# CTR-Lower-Main-Board-Rev-B-Sensors-4.net
KiCad netlist of a schematic drawn in Altium Designer
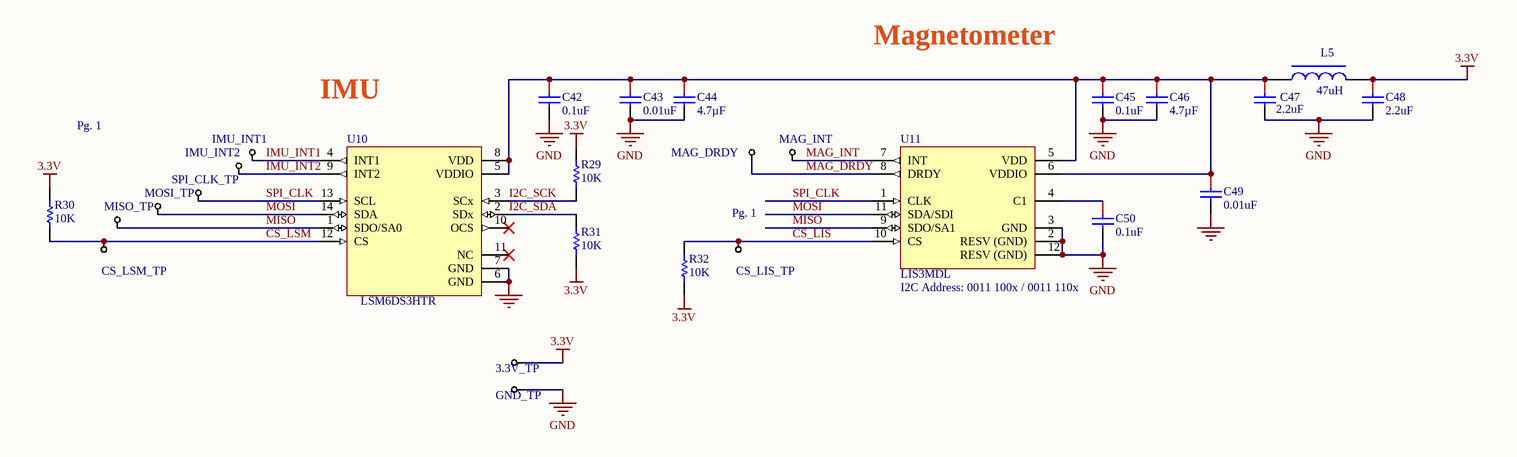
[diagram p0: CTR-Lower-Main-Board-Rev-B-Sensors-4.SchDoc]

(export (version "E")
  (design (tool "Eeschema 10.0.6"))
  (components
    (comp (ref "3.3V_TP")
      (value "3V")
      (footprint "TestPoint-TH 35 mil")
      (description "Test Point")
      (libsource (lib "OLogic-Misc") (part "TestPoint, small"))
    )
    (comp (ref "C42")
      (value "0.1uF")
      (footprint "CAPC0402(1005)_N")
      (description "0.1uF 0402 50V")
      (fields
        (field (name "MANUFACTURER") "TDK Corporation")
        (field (name "MANUFACTURER PART NUMBER") "CGA2B3X7R1H104K050BB")
        (field (name "CREATOR") "osman")
      )
      (libsource (lib "OLogic-Passive") (part "CAP CER 0.1UF 50V 10% X7R 0402"))
    )
    (comp (ref "C43")
      (value "0.01uF")
      (footprint "CAPC0402(1005)_N")
      (description "0.01uF 0402")
      (fields
        (field (name "MANUFACTURER") "Murata Electronics North America")
        (field (name "MANUFACTURER PART NUMBER") "GRM155R71E103KA01D")
      )
      (libsource (lib "OLogic-Passive") (part "CAP CER 0.01UF 25V 10% X5R 0402"))
    )
    (comp (ref "C44")
      (value "4.7UF 0603")
      (footprint "CAPC0603(1608)_L")
      (fields
        (field (name "MANUFACTURER") "Taiyo Yuden")
        (field (name "MANUFACTURER PART NUMBER") "EMK107ABJ475KA-T")
        (field (name "TOLERANCE") "±10%")
        (field (name "CAPACITANCE") "4.7µF")
        (field (name "CREATOR") "osman")
      )
      (libsource (lib "OLogic-Passive") (part "CAP CER 4.7UF 16V 10% X5R 0603"))
    )
    (comp (ref "C45")
      (value "0.1uF")
      (footprint "CAPC0402(1005)_N")
      (description "0.1uF 0402 50V")
      (fields
        (field (name "MANUFACTURER") "TDK Corporation")
        (field (name "MANUFACTURER PART NUMBER") "CGA2B3X7R1H104K050BB")
        (field (name "CREATOR") "osman")
      )
      (libsource (lib "OLogic-Passive") (part "CAP CER 0.1UF 50V 10% X7R 0402"))
    )
    (comp (ref "C46")
      (value "4.7UF 0603")
      (footprint "CAPC0603(1608)_L")
      (fields
        (field (name "MANUFACTURER") "Taiyo Yuden")
        (field (name "MANUFACTURER PART NUMBER") "EMK107ABJ475KA-T")
        (field (name "TOLERANCE") "±10%")
        (field (name "CAPACITANCE") "4.7µF")
        (field (name "CREATOR") "osman")
      )
      (libsource (lib "OLogic-Passive") (part "CAP CER 4.7UF 16V 10% X5R 0603"))
    )
    (comp (ref "C47")
      (value "2.2uF")
      (footprint "CAPC0402(1005)_N")
      (description "2.2uF 0402")
      (fields
        (field (name "MANUFACTURER") "TDK Corporation")
        (field (name "MANUFACTURER PART NUMBER") "C1005X5R1V225K050BC")
        (field (name "CREATOR") "osman")
      )
      (libsource (lib "OLogic-Passive") (part "CAP CER 2.2UF 35V 10% X5R 0402"))
    )
    (comp (ref "C48")
      (value "2.2uF")
      (footprint "CAPC0402(1005)_N")
      (description "2.2uF 0402")
      (fields
        (field (name "MANUFACTURER") "TDK Corporation")
        (field (name "MANUFACTURER PART NUMBER") "C1005X5R1V225K050BC")
        (field (name "CREATOR") "osman")
      )
      (libsource (lib "OLogic-Passive") (part "CAP CER 2.2UF 35V 10% X5R 0402"))
    )
    (comp (ref "C49")
      (value "0.01uF")
      (footprint "CAPC0402(1005)_N")
      (description "0.01uF 0402")
      (fields
        (field (name "MANUFACTURER") "Murata Electronics North America")
        (field (name "MANUFACTURER PART NUMBER") "GRM155R71E103KA01D")
      )
      (libsource (lib "OLogic-Passive") (part "CAP CER 0.01UF 25V 10% X5R 0402"))
    )
    (comp (ref "C50")
      (value "0.1uF")
      (footprint "CAPC0402(1005)_N")
      (description "0.1uF 0402 50V")
      (fields
        (field (name "MANUFACTURER") "TDK Corporation")
        (field (name "MANUFACTURER PART NUMBER") "CGA2B3X7R1H104K050BB")
        (field (name "CREATOR") "osman")
      )
      (libsource (lib "OLogic-Passive") (part "CAP CER 0.1UF 50V 10% X7R 0402"))
    )
    (comp (ref "CS_LIS_TP")
      (value "Test Point")
      (footprint "TestPoint-TH 42 mil")
      (libsource (lib "OLogic-Misc") (part "TestPoint, small"))
    )
    (comp (ref "CS_LSM_TP")
      (value "Test Point")
      (footprint "TestPoint-TH 42 mil")
      (libsource (lib "OLogic-Misc") (part "TestPoint, small"))
    )
    (comp (ref "GND_TP")
      (value "GND")
      (footprint "TestPoint-TH 35 mil")
      (description "Test Point")
      (libsource (lib "OLogic-Misc") (part "TestPoint, small"))
    )
    (comp (ref "IMU_INT1")
      (value "Test Point")
      (footprint "TestPoint-TH 42 mil")
      (libsource (lib "OLogic-Misc") (part "TestPoint, small"))
    )
    (comp (ref "IMU_INT2")
      (value "Test Point")
      (footprint "TestPoint-TH 42 mil")
      (libsource (lib "OLogic-Misc") (part "TestPoint, small"))
    )
    (comp (ref "L5")
      (value "47uH")
      (footprint "IND-2012 Chip")
      (description "47uH 0805")
      (fields
        (field (name "MANUFACTURER") "TDK Corporation")
        (field (name "MANUFACTURER PART NUMBER") "MLZ2012M470WT000")
      )
      (libsource (lib "OLogic-Passive") (part "INDUCTOR MULTILAYER 47UH 100mA 0805"))
    )
    (comp (ref "MAG_DRDY")
      (value "Test Point")
      (footprint "TestPoint-TH 42 mil")
      (libsource (lib "OLogic-Misc") (part "TestPoint, small"))
    )
    (comp (ref "MAG_INT")
      (value "Test Point")
      (footprint "TestPoint-TH 42 mil")
      (libsource (lib "OLogic-Misc") (part "TestPoint, small"))
    )
    (comp (ref "MISO_TP")
      (value "Test Point")
      (footprint "TestPoint-TH 42 mil")
      (libsource (lib "OLogic-Misc") (part "TestPoint, small"))
    )
    (comp (ref "MOSI_TP")
      (value "Test Point")
      (footprint "TestPoint-TH 42 mil")
      (libsource (lib "OLogic-Misc") (part "TestPoint, small"))
    )
    (comp (ref "R29")
      (value "10K")
      (footprint "RESC0402(1005)_N")
      (description "10K 0402")
      (fields
        (field (name "MANUFACTURER") "Panasonic Electronic Components")
        (field (name "MANUFACTURER PART NUMBER") "ERJ-2GEJ103X")
        (field (name "CREATOR") "ted")
      )
      (libsource (lib "OLogic-Passive") (part "RES 10K OHM 5% 1/10W 0402"))
    )
    (comp (ref "R30")
      (value "10K")
      (footprint "RESC0402(1005)_N")
      (description "10K 0402")
      (fields
        (field (name "MANUFACTURER") "Panasonic Electronic Components")
        (field (name "MANUFACTURER PART NUMBER") "ERJ-2GEJ103X")
        (field (name "CREATOR") "ted")
      )
      (libsource (lib "OLogic-Passive") (part "RES 10K OHM 5% 1/10W 0402"))
    )
    (comp (ref "R31")
      (value "10K")
      (footprint "RESC0402(1005)_N")
      (description "10K 0402")
      (fields
        (field (name "MANUFACTURER") "Panasonic Electronic Components")
        (field (name "MANUFACTURER PART NUMBER") "ERJ-2GEJ103X")
        (field (name "CREATOR") "ted")
      )
      (libsource (lib "OLogic-Passive") (part "RES 10K OHM 5% 1/10W 0402"))
    )
    (comp (ref "R32")
      (value "10K")
      (footprint "RESC0402(1005)_N")
      (description "10K 0402")
      (fields
        (field (name "MANUFACTURER") "Panasonic Electronic Components")
        (field (name "MANUFACTURER PART NUMBER") "ERJ-2GEJ103X")
        (field (name "CREATOR") "ted")
      )
      (libsource (lib "OLogic-Passive") (part "RES 10K OHM 5% 1/10W 0402"))
    )
    (comp (ref "SPI_CLK_TP")
      (value "Test Point")
      (footprint "TestPoint-TH 42 mil")
      (libsource (lib "OLogic-Misc") (part "TestPoint, small"))
    )
    (comp (ref "U10")
      (value "LSM6DS3")
      (footprint "LSM6DS3")
      (description "IMU ACCEL/GYRO/TEMP I2C/SPI LGA")
      (fields
        (field (name "MANUFACTURER") "STMicroelectronics")
        (field (name "MANUFACTURER PART NUMBER") "LSM6DS3HTR")
      )
      (libsource (lib "OLogic-Sensors") (part "LSM6DS3"))
    )
    (comp (ref "U11")
      (value "LIS3MDL")
      (footprint "LIS3MDL")
      (description "IC MAGNETOMETER 3-AXIS 12LGA")
      (fields
        (field (name "MANUFACTURER") "STMicroelectronics")
        (field (name "MANUFACTURER PART NUMBER") "LIS3MDL")
        (field (name "I2C ADDRESS") "0011 100x / 0011 110x")
        (field (name "CREATOR") "osman")
      )
      (libsource (lib "OLogic-Sensors") (part "LIS3MDL"))
    )
  )
  (nets
    (net (code "1") (name "/CS_LIS") (class "Default")
      (node (ref "CS_LIS_TP") (pin "1") (pinfunction "1_1") (pintype "passive"))
      (node (ref "R32") (pin "2") (pinfunction "2_2") (pintype "passive"))
      (node (ref "U11") (pin "10") (pinfunction "CS_10") (pintype "input"))
    )
    (net (code "2") (name "/CS_LSM") (class "Default")
      (node (ref "CS_LSM_TP") (pin "1") (pinfunction "1_1") (pintype "passive"))
      (node (ref "R30") (pin "1") (pinfunction "1_1") (pintype "passive"))
      (node (ref "U10") (pin "12") (pinfunction "CS_12") (pintype "input"))
    )
    (net (code "3") (name "/I2C_SCK") (class "Default")
      (node (ref "R29") (pin "1") (pinfunction "1_1") (pintype "passive"))
      (node (ref "U10") (pin "3") (pinfunction "SCx_3") (pintype "input"))
    )
    (net (code "4") (name "/I2C_SDA") (class "Default")
      (node (ref "R31") (pin "2") (pinfunction "2_2") (pintype "passive"))
      (node (ref "U10") (pin "2") (pinfunction "SDx_2") (pintype "bidirectional"))
    )
    (net (code "5") (name "/IMU_INT1") (class "Default")
      (node (ref "IMU_INT1") (pin "1") (pinfunction "1_1") (pintype "passive"))
      (node (ref "U10") (pin "4") (pinfunction "INT1_4") (pintype "output"))
    )
    (net (code "6") (name "/IMU_INT2") (class "Default")
      (node (ref "IMU_INT2") (pin "1") (pinfunction "1_1") (pintype "passive"))
      (node (ref "U10") (pin "9") (pinfunction "INT2_9") (pintype "output"))
    )
    (net (code "7") (name "/MAG_DRDY") (class "Default")
      (node (ref "MAG_DRDY") (pin "1") (pinfunction "1_1") (pintype "passive"))
      (node (ref "U11") (pin "8") (pinfunction "DRDY_8") (pintype "output"))
    )
    (net (code "8") (name "/MAG_INT") (class "Default")
      (node (ref "MAG_INT") (pin "1") (pinfunction "1_1") (pintype "passive"))
      (node (ref "U11") (pin "7") (pinfunction "INT_7") (pintype "output"))
    )
    (net (code "9") (name "/MISO") (class "Default")
      (node (ref "MISO_TP") (pin "1") (pinfunction "1_1") (pintype "passive"))
      (node (ref "U10") (pin "1") (pinfunction "SDO/SA0_1") (pintype "bidirectional"))
      (node (ref "U11") (pin "9") (pinfunction "SDO/SA1_9") (pintype "bidirectional"))
    )
    (net (code "10") (name "/MOSI") (class "Default")
      (node (ref "MOSI_TP") (pin "1") (pinfunction "1_1") (pintype "passive"))
      (node (ref "U10") (pin "14") (pinfunction "SDA_14") (pintype "bidirectional"))
      (node (ref "U11") (pin "11") (pinfunction "SDA/SDI_11") (pintype "bidirectional"))
    )
    (net (code "11") (name "/SPI_CLK") (class "Default")
      (node (ref "SPI_CLK_TP") (pin "1") (pinfunction "1_1") (pintype "passive"))
      (node (ref "U10") (pin "13") (pinfunction "SCL_13") (pintype "input"))
      (node (ref "U11") (pin "1") (pinfunction "CLK_1") (pintype "input"))
    )
    (net (code "12") (name "3.3V") (class "Default")
      (node (ref "3.3V_TP") (pin "1") (pinfunction "1_1") (pintype "passive"))
      (node (ref "C48") (pin "1") (pinfunction "1_1") (pintype "passive"))
      (node (ref "L5") (pin "2") (pinfunction "2_2") (pintype "passive"))
      (node (ref "R29") (pin "2") (pinfunction "2_2") (pintype "passive"))
      (node (ref "R30") (pin "2") (pinfunction "2_2") (pintype "passive"))
      (node (ref "R31") (pin "1") (pinfunction "1_1") (pintype "passive"))
      (node (ref "R32") (pin "1") (pinfunction "1_1") (pintype "passive"))
    )
    (net (code "13") (name "GND") (class "Default")
      (node (ref "C42") (pin "2") (pinfunction "2_2") (pintype "passive"))
      (node (ref "C43") (pin "2") (pinfunction "2_2") (pintype "passive"))
      (node (ref "C44") (pin "2") (pinfunction "2_2") (pintype "passive"))
      (node (ref "C45") (pin "2") (pinfunction "2_2") (pintype "passive"))
      (node (ref "C46") (pin "2") (pinfunction "2_2") (pintype "passive"))
      (node (ref "C47") (pin "2") (pinfunction "2_2") (pintype "passive"))
      (node (ref "C48") (pin "2") (pinfunction "2_2") (pintype "passive"))
      (node (ref "C49") (pin "2") (pinfunction "2_2") (pintype "passive"))
      (node (ref "C50") (pin "2") (pinfunction "2_2") (pintype "passive"))
      (node (ref "GND_TP") (pin "1") (pinfunction "1_1") (pintype "passive"))
      (node (ref "U10") (pin "6") (pinfunction "GND_6") (pintype "power_in"))
      (node (ref "U10") (pin "7") (pinfunction "GND_7") (pintype "power_in"))
      (node (ref "U11") (pin "12") (pinfunction "RESV_(GND)_12") (pintype "power_in"))
      (node (ref "U11") (pin "2") (pinfunction "RESV_(GND)_2") (pintype "power_in"))
      (node (ref "U11") (pin "3") (pinfunction "GND_3") (pintype "power_in"))
    )
    (net (code "14") (name "Net-(U10-VDD)") (class "Default")
      (node (ref "C42") (pin "1") (pinfunction "1_1") (pintype "passive"))
      (node (ref "C43") (pin "1") (pinfunction "1_1") (pintype "passive"))
      (node (ref "C44") (pin "1") (pinfunction "1_1") (pintype "passive"))
      (node (ref "C45") (pin "1") (pinfunction "1_1") (pintype "passive"))
      (node (ref "C46") (pin "1") (pinfunction "1_1") (pintype "passive"))
      (node (ref "C47") (pin "1") (pinfunction "1_1") (pintype "passive"))
      (node (ref "C49") (pin "1") (pinfunction "1_1") (pintype "passive"))
      (node (ref "L5") (pin "1") (pinfunction "1_1") (pintype "passive"))
      (node (ref "U10") (pin "5") (pinfunction "VDDIO_5") (pintype "power_in"))
      (node (ref "U10") (pin "8") (pinfunction "VDD_8") (pintype "power_in"))
      (node (ref "U11") (pin "5") (pinfunction "VDD_5") (pintype "power_in"))
      (node (ref "U11") (pin "6") (pinfunction "VDDIO_6") (pintype "power_in"))
    )
    (net (code "15") (name "Net-(U11-C1)") (class "Default")
      (node (ref "C50") (pin "1") (pinfunction "1_1") (pintype "passive"))
      (node (ref "U11") (pin "4") (pinfunction "C1_4") (pintype "power_in"))
    )
    (net (code "16") (name "unconnected-(U10-NC-Pad11)") (class "Default")
      (node (ref "U10") (pin "11") (pinfunction "NC_11") (pintype "passive+no_connect"))
    )
    (net (code "17") (name "unconnected-(U10-OCS-Pad10)") (class "Default")
      (node (ref "U10") (pin "10") (pinfunction "OCS_10") (pintype "output+no_connect"))
    )
  )
)
